# powerBoard_v2.net
KiCad netlist of a schematic drawn in EAGLE
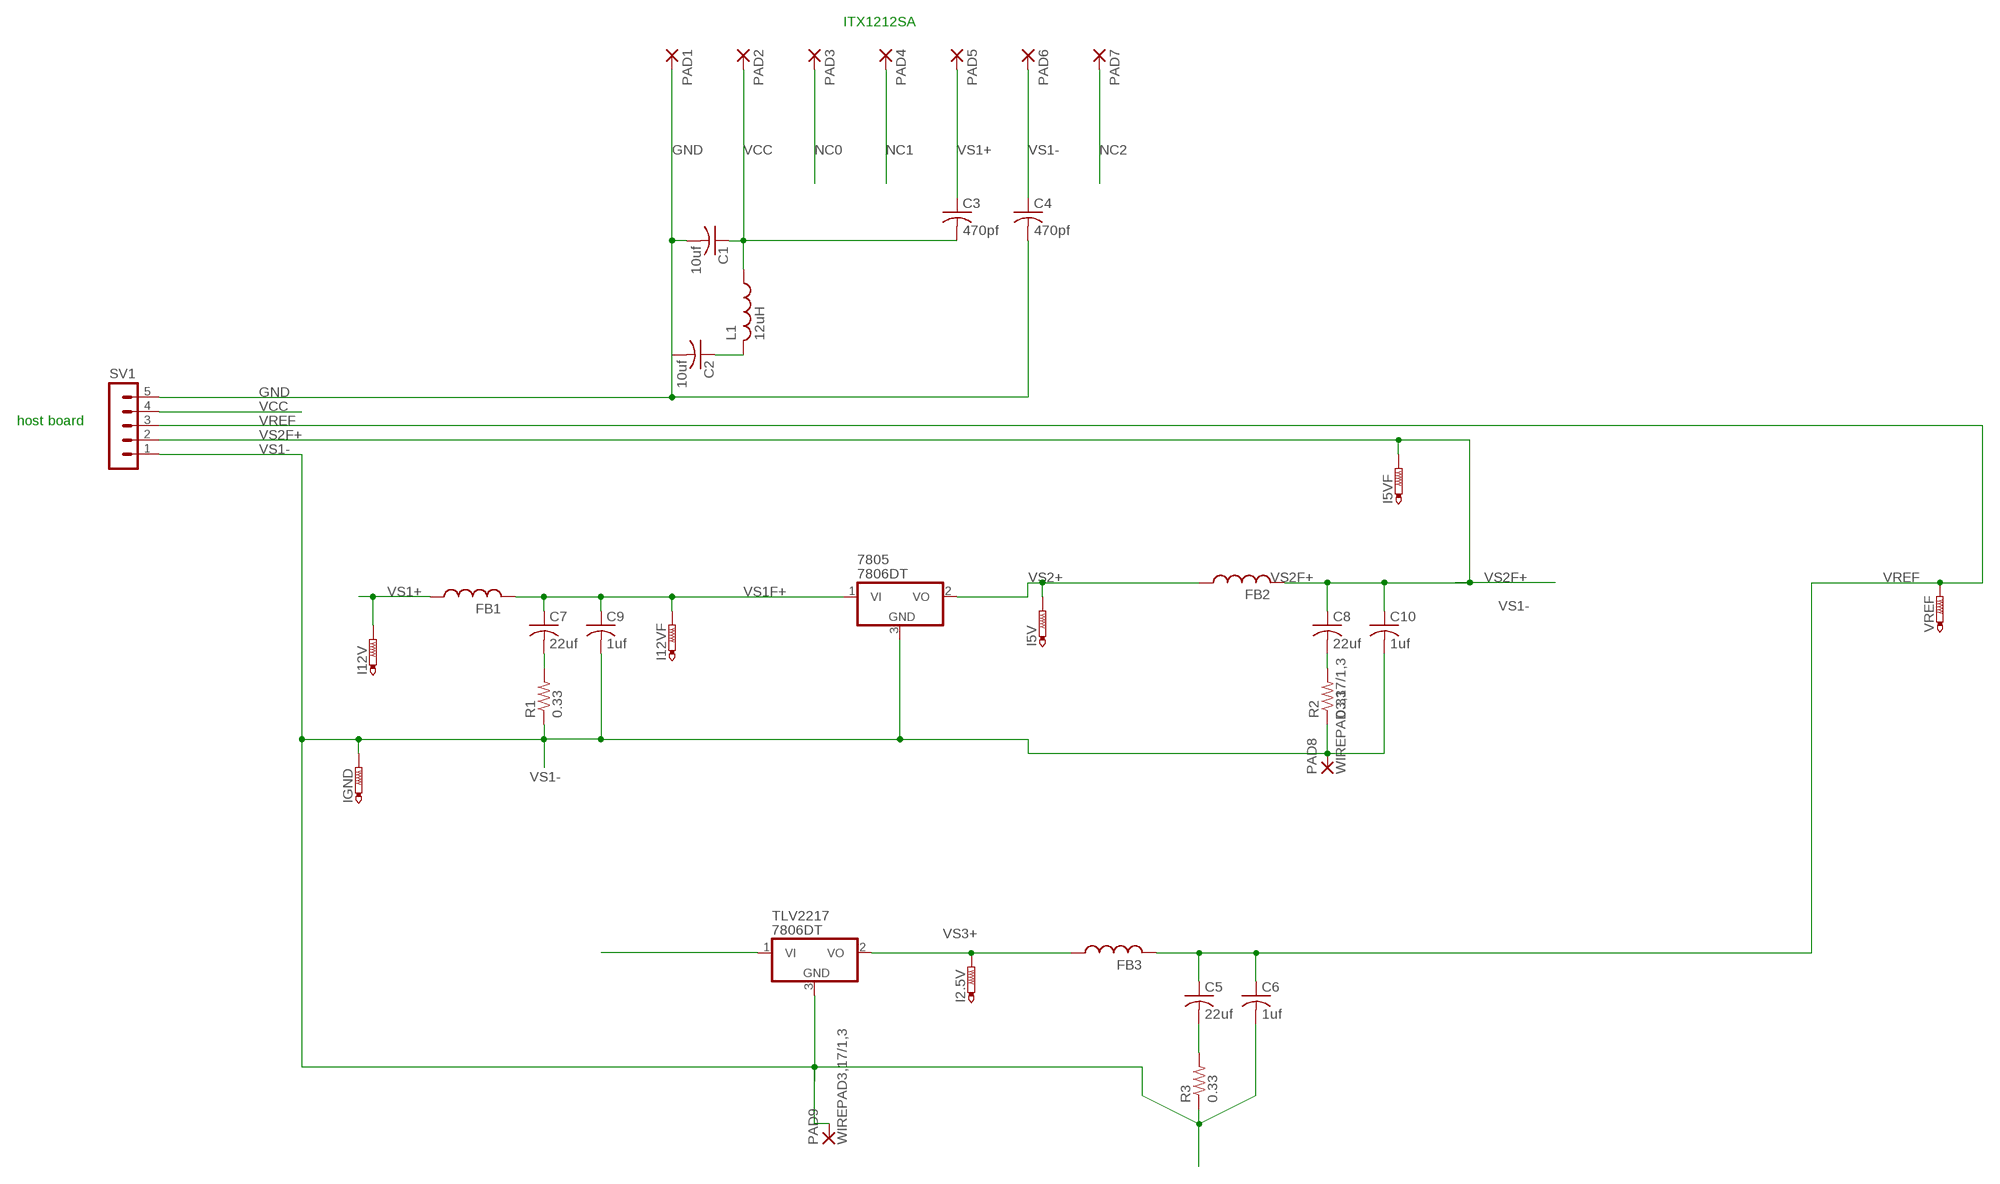
[diagram p0: schematic, sheet 1]

(export (version "E")
  (design (tool "Eeschema 10.0.6"))
  (components
    (comp (ref "7805")
      (value "7806DT")
      (footprint "eagle-import:TO252")
      (libsource (lib "eagle-import") (part "78DT06"))
    )
    (comp (ref "C1")
      (value "10uf")
      (footprint "eagle-import:C0805K")
      (libsource (lib "eagle-import") (part "C-USC0805K"))
    )
    (comp (ref "C2")
      (value "10uf")
      (footprint "eagle-import:C0805K")
      (libsource (lib "eagle-import") (part "C-USC0805K"))
    )
    (comp (ref "C3")
      (value "470pf")
      (footprint "eagle-import:C0805K")
      (libsource (lib "eagle-import") (part "C-USC0805K"))
    )
    (comp (ref "C4")
      (value "470pf")
      (footprint "eagle-import:C0805K")
      (libsource (lib "eagle-import") (part "C-USC0805K"))
    )
    (comp (ref "C5")
      (value "22uf")
      (footprint "eagle-import:C0805K")
      (libsource (lib "eagle-import") (part "C-USC0805K"))
    )
    (comp (ref "C6")
      (value "1uf")
      (footprint "eagle-import:C0805K")
      (libsource (lib "eagle-import") (part "C-USC0805K"))
    )
    (comp (ref "C7")
      (value "22uf")
      (footprint "eagle-import:C0805K")
      (libsource (lib "eagle-import") (part "C-USC0805K"))
    )
    (comp (ref "C8")
      (value "22uf")
      (footprint "eagle-import:C0805K")
      (libsource (lib "eagle-import") (part "C-USC0805K"))
    )
    (comp (ref "C9")
      (value "1uf")
      (footprint "eagle-import:C0805K")
      (libsource (lib "eagle-import") (part "C-USC0805K"))
    )
    (comp (ref "C10")
      (value "1uf")
      (footprint "eagle-import:C0805K")
      (libsource (lib "eagle-import") (part "C-USC0805K"))
    )
    (comp (ref "FB1")
      (value "L-USL2012C")
      (footprint "eagle-import:L2012C")
      (libsource (lib "eagle-import") (part "L-USL2012C"))
    )
    (comp (ref "FB2")
      (value "L-USL2012C")
      (footprint "eagle-import:L2012C")
      (libsource (lib "eagle-import") (part "L-USL2012C"))
    )
    (comp (ref "FB3")
      (value "L-USL2012C")
      (footprint "eagle-import:L2012C")
      (libsource (lib "eagle-import") (part "L-USL2012C"))
    )
    (comp (ref "I2.5V")
      (value "PTR1PAD1-13")
      (footprint "eagle-import:P1-13")
      (libsource (lib "eagle-import") (part "PTR1PAD1-13"))
    )
    (comp (ref "I5V")
      (value "PTR1PAD1-13")
      (footprint "eagle-import:P1-13")
      (libsource (lib "eagle-import") (part "PTR1PAD1-13"))
    )
    (comp (ref "I5VF")
      (value "PTR1PAD1-13")
      (footprint "eagle-import:P1-13")
      (libsource (lib "eagle-import") (part "PTR1PAD1-13"))
    )
    (comp (ref "I12V")
      (value "PTR1PAD1-13")
      (footprint "eagle-import:P1-13")
      (libsource (lib "eagle-import") (part "PTR1PAD1-13"))
    )
    (comp (ref "I12VF")
      (value "PTR1PAD1-13")
      (footprint "eagle-import:P1-13")
      (libsource (lib "eagle-import") (part "PTR1PAD1-13"))
    )
    (comp (ref "IGND")
      (value "PTR1PAD1-13")
      (footprint "eagle-import:P1-13")
      (libsource (lib "eagle-import") (part "PTR1PAD1-13"))
    )
    (comp (ref "L1")
      (value "12uH")
      (footprint "eagle-import:L2012C")
      (libsource (lib "eagle-import") (part "resistor_L-USL2012C"))
    )
    (comp (ref "PAD1")
      (value "SMD2")
      (footprint "eagle-import:SMD1,27-2,54")
      (libsource (lib "eagle-import") (part "SMD2"))
    )
    (comp (ref "PAD2")
      (value "SMD2")
      (footprint "eagle-import:SMD1,27-2,54")
      (libsource (lib "eagle-import") (part "SMD2"))
    )
    (comp (ref "PAD3")
      (value "SMD2")
      (footprint "eagle-import:SMD1,27-2,54")
      (libsource (lib "eagle-import") (part "SMD2"))
    )
    (comp (ref "PAD4")
      (value "SMD2")
      (footprint "eagle-import:SMD1,27-2,54")
      (libsource (lib "eagle-import") (part "SMD2"))
    )
    (comp (ref "PAD5")
      (value "SMD2")
      (footprint "eagle-import:SMD1,27-2,54")
      (libsource (lib "eagle-import") (part "SMD2"))
    )
    (comp (ref "PAD6")
      (value "SMD2")
      (footprint "eagle-import:SMD1,27-2,54")
      (libsource (lib "eagle-import") (part "SMD2"))
    )
    (comp (ref "PAD7")
      (value "SMD2")
      (footprint "eagle-import:SMD1,27-2,54")
      (libsource (lib "eagle-import") (part "SMD2"))
    )
    (comp (ref "PAD8")
      (value "WIREPAD3,17/1,3")
      (footprint "eagle-import:3,17_1,3")
      (libsource (lib "eagle-import") (part "WIREPAD3,17/1,3"))
    )
    (comp (ref "PAD9")
      (value "WIREPAD3,17/1,3")
      (footprint "eagle-import:3,17_1,3")
      (libsource (lib "eagle-import") (part "WIREPAD3,17/1,3"))
    )
    (comp (ref "R1")
      (value "0.33")
      (footprint "eagle-import:R2012W")
      (libsource (lib "eagle-import") (part "R-US_R2012W"))
    )
    (comp (ref "R2")
      (value "0.33")
      (footprint "eagle-import:R2012W")
      (libsource (lib "eagle-import") (part "R-US_R2012W"))
    )
    (comp (ref "R3")
      (value "0.33")
      (footprint "eagle-import:R2012W")
      (libsource (lib "eagle-import") (part "R-US_R2012W"))
    )
    (comp (ref "SV1")
      (value "MA05-1")
      (footprint "eagle-import:MA05-1")
      (libsource (lib "eagle-import") (part "MA05-1"))
    )
    (comp (ref "TLV2217")
      (value "7806DT")
      (footprint "eagle-import:TO252")
      (libsource (lib "eagle-import") (part "78DT06"))
    )
    (comp (ref "VREF")
      (value "PTR1PAD1-13")
      (footprint "eagle-import:P1-13")
      (libsource (lib "eagle-import") (part "PTR1PAD1-13"))
    )
  )
  (nets
    (net (code "1") (name "/GND") (class "Default")
      (node (ref "C1") (pin "2") (pinfunction "2_2") (pintype "passive"))
      (node (ref "C2") (pin "2") (pinfunction "2_2") (pintype "passive"))
      (node (ref "C4") (pin "2") (pinfunction "2_2") (pintype "passive"))
      (node (ref "PAD1") (pin "1") (pinfunction "P_1") (pintype "passive"))
      (node (ref "SV1") (pin "5") (pinfunction "5_5") (pintype "passive"))
    )
    (net (code "2") (name "/NC0") (class "Default")
      (node (ref "PAD3") (pin "1") (pinfunction "P_1") (pintype "passive"))
    )
    (net (code "3") (name "/NC1") (class "Default")
      (node (ref "PAD4") (pin "1") (pinfunction "P_1") (pintype "passive"))
    )
    (net (code "4") (name "/NC2") (class "Default")
      (node (ref "PAD7") (pin "1") (pinfunction "P_1") (pintype "passive"))
    )
    (net (code "5") (name "/VCC") (class "Default")
      (node (ref "C1") (pin "1") (pinfunction "1_1") (pintype "passive"))
      (node (ref "C3") (pin "2") (pinfunction "2_2") (pintype "passive"))
      (node (ref "L1") (pin "1") (pinfunction "1_1") (pintype "passive"))
      (node (ref "PAD2") (pin "1") (pinfunction "P_1") (pintype "passive"))
      (node (ref "SV1") (pin "4") (pinfunction "4_4") (pintype "passive"))
    )
    (net (code "6") (name "/VREF") (class "Default")
      (node (ref "C5") (pin "1") (pinfunction "1_1") (pintype "passive"))
      (node (ref "C6") (pin "1") (pinfunction "1_1") (pintype "passive"))
      (node (ref "FB3") (pin "2") (pinfunction "2_2") (pintype "passive"))
      (node (ref "SV1") (pin "3") (pinfunction "3_3") (pintype "passive"))
      (node (ref "VREF") (pin "TP") (pinfunction "TP_TP") (pintype "input"))
    )
    (net (code "7") (name "/VS1+") (class "Default")
      (node (ref "C3") (pin "1") (pinfunction "1_1") (pintype "passive"))
      (node (ref "FB1") (pin "1") (pinfunction "1_1") (pintype "passive"))
      (node (ref "I12V") (pin "TP") (pinfunction "TP_TP") (pintype "input"))
      (node (ref "PAD5") (pin "1") (pinfunction "P_1") (pintype "passive"))
    )
    (net (code "8") (name "/VS1-") (class "Default")
      (node (ref "7805") (pin "3") (pinfunction "GND_3") (pintype "passive"))
      (node (ref "C10") (pin "2") (pinfunction "2_2") (pintype "passive"))
      (node (ref "C4") (pin "1") (pinfunction "1_1") (pintype "passive"))
      (node (ref "C6") (pin "2") (pinfunction "2_2") (pintype "passive"))
      (node (ref "C9") (pin "2") (pinfunction "2_2") (pintype "passive"))
      (node (ref "IGND") (pin "TP") (pinfunction "TP_TP") (pintype "input"))
      (node (ref "PAD6") (pin "1") (pinfunction "P_1") (pintype "passive"))
      (node (ref "PAD8") (pin "1") (pinfunction "P_1") (pintype "passive"))
      (node (ref "PAD9") (pin "1") (pinfunction "P_1") (pintype "passive"))
      (node (ref "R1") (pin "1") (pinfunction "1_1") (pintype "passive"))
      (node (ref "R2") (pin "1") (pinfunction "1_1") (pintype "passive"))
      (node (ref "R3") (pin "1") (pinfunction "1_1") (pintype "passive"))
      (node (ref "SV1") (pin "1") (pinfunction "1_1") (pintype "passive"))
      (node (ref "TLV2217") (pin "3") (pinfunction "GND_3") (pintype "passive"))
    )
    (net (code "9") (name "/VS1F+") (class "Default")
      (node (ref "7805") (pin "1") (pinfunction "VI_1") (pintype "input"))
      (node (ref "C7") (pin "1") (pinfunction "1_1") (pintype "passive"))
      (node (ref "C9") (pin "1") (pinfunction "1_1") (pintype "passive"))
      (node (ref "FB1") (pin "2") (pinfunction "2_2") (pintype "passive"))
      (node (ref "I12VF") (pin "TP") (pinfunction "TP_TP") (pintype "input"))
      (node (ref "TLV2217") (pin "1") (pinfunction "VI_1") (pintype "input"))
    )
    (net (code "10") (name "/VS2+") (class "Default")
      (node (ref "7805") (pin "2") (pinfunction "VO_2") (pintype "passive"))
      (node (ref "FB2") (pin "1") (pinfunction "1_1") (pintype "passive"))
      (node (ref "I5V") (pin "TP") (pinfunction "TP_TP") (pintype "input"))
    )
    (net (code "11") (name "/VS2F+") (class "Default")
      (node (ref "C10") (pin "1") (pinfunction "1_1") (pintype "passive"))
      (node (ref "C8") (pin "1") (pinfunction "1_1") (pintype "passive"))
      (node (ref "FB2") (pin "2") (pinfunction "2_2") (pintype "passive"))
      (node (ref "I5VF") (pin "TP") (pinfunction "TP_TP") (pintype "input"))
      (node (ref "SV1") (pin "2") (pinfunction "2_2") (pintype "passive"))
    )
    (net (code "12") (name "/VS3+") (class "Default")
      (node (ref "FB3") (pin "1") (pinfunction "1_1") (pintype "passive"))
      (node (ref "I2.5V") (pin "TP") (pinfunction "TP_TP") (pintype "input"))
      (node (ref "TLV2217") (pin "2") (pinfunction "VO_2") (pintype "passive"))
    )
    (net (code "13") (name "Net-(C2-Pad1)") (class "Default")
      (node (ref "C2") (pin "1") (pinfunction "1_1") (pintype "passive"))
      (node (ref "L1") (pin "2") (pinfunction "2_2") (pintype "passive"))
    )
    (net (code "14") (name "Net-(C5-Pad2)") (class "Default")
      (node (ref "C5") (pin "2") (pinfunction "2_2") (pintype "passive"))
      (node (ref "R3") (pin "2") (pinfunction "2_2") (pintype "passive"))
    )
    (net (code "15") (name "Net-(C7-Pad2)") (class "Default")
      (node (ref "C7") (pin "2") (pinfunction "2_2") (pintype "passive"))
      (node (ref "R1") (pin "2") (pinfunction "2_2") (pintype "passive"))
    )
    (net (code "16") (name "Net-(C8-Pad2)") (class "Default")
      (node (ref "C8") (pin "2") (pinfunction "2_2") (pintype "passive"))
      (node (ref "R2") (pin "2") (pinfunction "2_2") (pintype "passive"))
    )
  )
)
